# Sheet1.net
KiCad netlist of a schematic drawn in Altium Designer
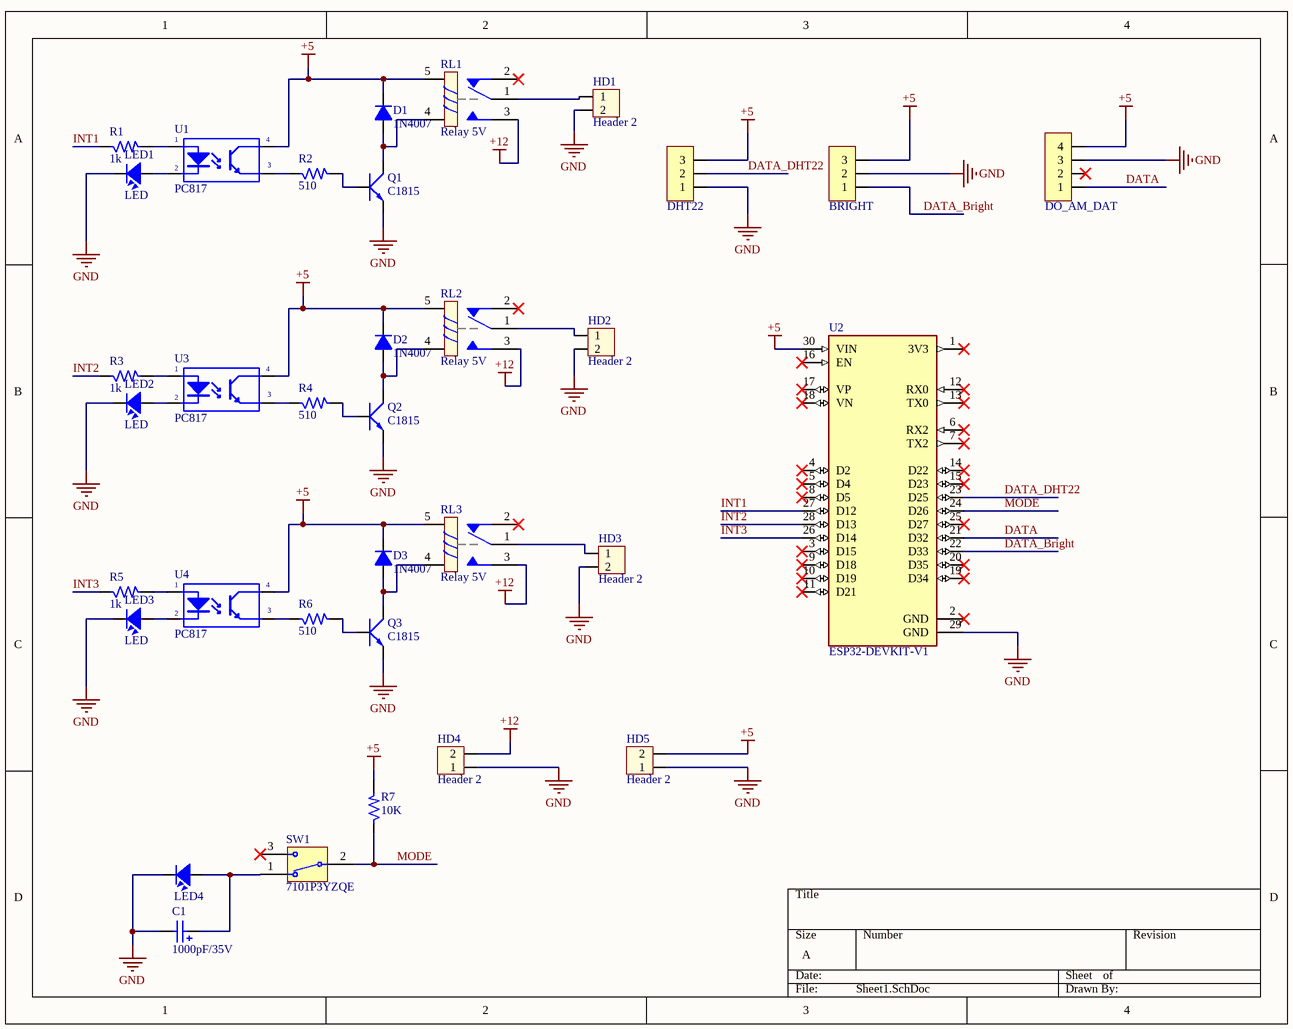
[diagram p0: Sheet1.SchDoc]

(export (version "E")
  (design (tool "Eeschema 10.0.6"))
  (components
    (comp (ref "C1")
      (value "1000pF/35V")
      (footprint "CP2/5")
      (description "Polarized Capacitor (Surface Mount)")
      (fields (field (name "Comment") "Cap Pol3") (field (name "PUBLISHER") "Altium Limited"))
      (libsource (lib "myLib_v1") (part "Cap Pol3"))
    )
    (comp (ref "D1")
      (value "1N4007")
      (footprint "D2A")
      (description "Diode 1A")
      (libsource (lib "syhaunguyen") (part "D1A"))
    )
    (comp (ref "D2")
      (value "1N4007")
      (footprint "D2A")
      (description "Diode 1A")
      (libsource (lib "syhaunguyen") (part "D1A"))
    )
    (comp (ref "D3")
      (value "1N4007")
      (footprint "D2A")
      (description "Diode 1A")
      (libsource (lib "syhaunguyen") (part "D1A"))
    )
    (comp (ref "HD1")
      (value "Header 2")
      (footprint "HED2")
      (description "Header 2 (Green)")
      (libsource (lib "") (part "Hed2_1"))
    )
    (comp (ref "HD2")
      (value "Header 2")
      (footprint "HED2")
      (description "Header 2 (Green)")
      (libsource (lib "") (part "Hed2_1"))
    )
    (comp (ref "HD3")
      (value "Header 2")
      (footprint "HED2")
      (description "Header 2 (Green)")
      (libsource (lib "") (part "Hed2_1"))
    )
    (comp (ref "HD4")
      (value "Header 2")
      (footprint "HED2")
      (description "Header 2 (Green)")
      (libsource (lib "syhaunguyen") (part "Hed2"))
    )
    (comp (ref "HD5")
      (value "Header 2")
      (footprint "HED2")
      (description "Header 2 (Green)")
      (libsource (lib "syhaunguyen") (part "Hed2"))
    )
    (comp (ref "JP1")
      (value "DO_AM_DAT")
      (footprint "JP 1x4 CT")
      (description "Cắm")
      (libsource (lib "Altium_Lib_by_KhueNguyenCreator") (part "JP 1x4 2.54 Cai Thang"))
    )
    (comp (ref "JP2")
      (value "DHT22")
      (footprint "JP 1x3 CT")
      (description "Cắm")
      (libsource (lib "Altium_Lib_by_KhueNguyenCreator") (part "JP 1x3 2.54 Cai Thang"))
    )
    (comp (ref "JP3")
      (value "BRIGHT")
      (footprint "JP 1x3 CT")
      (description "Cắm")
      (libsource (lib "Altium_Lib_by_KhueNguyenCreator") (part "JP 1x3 2.54 Cai Thang"))
    )
    (comp (ref "LED1")
      (value "LED")
      (footprint "LED-5TRED")
      (description "LED Single colour Green and Red")
      (libsource (lib "syhaunguyen") (part "LED"))
    )
    (comp (ref "LED2")
      (value "LED")
      (footprint "LED-5TRED")
      (description "LED Single colour Green and Red")
      (libsource (lib "syhaunguyen") (part "LED"))
    )
    (comp (ref "LED3")
      (value "LED")
      (footprint "LED-5TRED")
      (description "LED Single colour Green and Red")
      (libsource (lib "syhaunguyen") (part "LED"))
    )
    (comp (ref "LED4")
      (value "LED")
      (footprint "LED-5-RED")
      (description "LED Single colour Green and Red")
      (libsource (lib "Thuvien3D") (part "LED"))
    )
    (comp (ref "Q1")
      (value "C1815")
      (footprint "QTO-92")
      (description "NPN 600mW, ECB")
      (libsource (lib "syhaunguyen") (part "C1815"))
    )
    (comp (ref "Q2")
      (value "C1815")
      (footprint "QTO-92")
      (description "NPN 600mW, ECB")
      (libsource (lib "syhaunguyen") (part "C1815"))
    )
    (comp (ref "Q3")
      (value "C1815")
      (footprint "QTO-92")
      (description "NPN 600mW, ECB")
      (libsource (lib "syhaunguyen") (part "C1815"))
    )
    (comp (ref "R1")
      (value "1k")
      (footprint "DIEN TRO 1/4 W")
      (description "Resistor 1/4W")
      (libsource (lib "Cty1") (part "Res"))
    )
    (comp (ref "R2")
      (value "510")
      (footprint "DIEN TRO 1/4 W")
      (description "Resistor 1/4W")
      (libsource (lib "Cty1") (part "Res"))
    )
    (comp (ref "R3")
      (value "1k")
      (footprint "DIEN TRO 1/4 W")
      (description "Resistor 1/4W")
      (libsource (lib "Cty1") (part "Res"))
    )
    (comp (ref "R4")
      (value "510")
      (footprint "DIEN TRO 1/4 W")
      (description "Resistor 1/4W")
      (libsource (lib "Cty1") (part "Res"))
    )
    (comp (ref "R5")
      (value "1k")
      (footprint "DIEN TRO 1/4 W")
      (description "Resistor 1/4W")
      (libsource (lib "Cty1") (part "Res"))
    )
    (comp (ref "R6")
      (value "510")
      (footprint "DIEN TRO 1/4 W")
      (description "Resistor 1/4W")
      (libsource (lib "Cty1") (part "Res"))
    )
    (comp (ref "R7")
      (value "10K")
      (footprint "DIEN TRO 1/4 W")
      (description "Resistor 1/4W")
      (libsource (lib "Cty1") (part "Res"))
    )
    (comp (ref "RL1")
      (value "Relay 5V")
      (footprint "RL_SPDT_10A")
      (description "Relay SPDT,10A - 12VDC 5 Pin")
      (libsource (lib "syhaunguyen") (part "Relay 1"))
    )
    (comp (ref "RL2")
      (value "Relay 5V")
      (footprint "RL_SPDT_10A")
      (description "Relay SPDT,10A - 12VDC 5 Pin")
      (libsource (lib "syhaunguyen") (part "Relay 1"))
    )
    (comp (ref "RL3")
      (value "Relay 5V")
      (footprint "RL_SPDT_10A")
      (description "Relay SPDT,10A - 12VDC 5 Pin")
      (libsource (lib "syhaunguyen") (part "Relay 1"))
    )
    (comp (ref "SW1")
      (value "7101P3YZQE")
      (footprint "SW_TOGGLE_7101P3YZQE")
      (description "SWITCH TOGGLE SPDT 5A 120V")
      (fields (field (name "MANUFACTURER") "C&K"))
      (libsource (lib "KhanhBK_SCH_Lib_6") (part "SW_TOGGLE_7101P3YZQE"))
    )
    (comp (ref "U1")
      (value "PC817")
      (footprint "DIP4/W0.3")
      (description "Single Opto")
      (libsource (lib "syhaunguyen") (part "PC817"))
    )
    (comp (ref "U2")
      (value "ESP32-DEVKIT-V1")
      (footprint "MODULE_ESP32_DEVKIT_V1")
      (fields (field (name "MF") "Do it"))
      (libsource (lib "ESP32-DEVKIT-V1") (part "ESP32-DEVKIT-V1"))
    )
    (comp (ref "U3")
      (value "PC817")
      (footprint "DIP4/W0.3")
      (description "Single Opto")
      (libsource (lib "syhaunguyen") (part "PC817"))
    )
    (comp (ref "U4")
      (value "PC817")
      (footprint "DIP4/W0.3")
      (description "Single Opto")
      (libsource (lib "syhaunguyen") (part "PC817"))
    )
  )
  (nets
    (net (code "1") (name "+5") (class "Default")
      (node (ref "D1") (pin "2") (pinfunction "K_2") (pintype "passive"))
      (node (ref "D2") (pin "2") (pinfunction "K_2") (pintype "passive"))
      (node (ref "D3") (pin "2") (pinfunction "K_2") (pintype "passive"))
      (node (ref "HD5") (pin "2") (pinfunction "2_2") (pintype "passive"))
      (node (ref "JP1") (pin "4") (pinfunction "4_4") (pintype "passive"))
      (node (ref "JP2") (pin "3") (pinfunction "3_3") (pintype "passive"))
      (node (ref "JP3") (pin "3") (pinfunction "3_3") (pintype "passive"))
      (node (ref "R7") (pin "2") (pinfunction "2_2") (pintype "passive"))
      (node (ref "RL1") (pin "5") (pinfunction "5_5") (pintype "passive"))
      (node (ref "RL2") (pin "5") (pinfunction "5_5") (pintype "passive"))
      (node (ref "RL3") (pin "5") (pinfunction "5_5") (pintype "passive"))
      (node (ref "U1") (pin "4") (pinfunction "C_4") (pintype "passive"))
      (node (ref "U2") (pin "30") (pinfunction "VIN_30") (pintype "input"))
      (node (ref "U3") (pin "4") (pinfunction "C_4") (pintype "passive"))
      (node (ref "U4") (pin "4") (pinfunction "C_4") (pintype "passive"))
    )
    (net (code "2") (name "+12") (class "Default")
      (node (ref "HD4") (pin "2") (pinfunction "2_2") (pintype "passive"))
      (node (ref "RL1") (pin "3") (pinfunction "3_3") (pintype "passive"))
      (node (ref "RL2") (pin "3") (pinfunction "3_3") (pintype "passive"))
      (node (ref "RL3") (pin "3") (pinfunction "3_3") (pintype "passive"))
    )
    (net (code "3") (name "/DATA") (class "Default")
      (node (ref "JP1") (pin "1") (pinfunction "1_1") (pintype "passive"))
      (node (ref "U2") (pin "21") (pinfunction "D32_21") (pintype "bidirectional"))
    )
    (net (code "4") (name "/DATA_Bright") (class "Default")
      (node (ref "JP3") (pin "1") (pinfunction "1_1") (pintype "passive"))
      (node (ref "U2") (pin "22") (pinfunction "D33_22") (pintype "bidirectional"))
    )
    (net (code "5") (name "/DATA_DHT22") (class "Default")
      (node (ref "JP2") (pin "2") (pinfunction "2_2") (pintype "passive"))
      (node (ref "U2") (pin "23") (pinfunction "D25_23") (pintype "bidirectional"))
    )
    (net (code "6") (name "/INT1") (class "Default")
      (node (ref "R1") (pin "1") (pinfunction "1_1") (pintype "passive"))
      (node (ref "U2") (pin "27") (pinfunction "D12_27") (pintype "bidirectional"))
    )
    (net (code "7") (name "/INT2") (class "Default")
      (node (ref "R3") (pin "1") (pinfunction "1_1") (pintype "passive"))
      (node (ref "U2") (pin "28") (pinfunction "D13_28") (pintype "bidirectional"))
    )
    (net (code "8") (name "/INT3") (class "Default")
      (node (ref "R5") (pin "1") (pinfunction "1_1") (pintype "passive"))
      (node (ref "U2") (pin "26") (pinfunction "D14_26") (pintype "bidirectional"))
    )
    (net (code "9") (name "/MODE") (class "Default")
      (node (ref "R7") (pin "1") (pinfunction "1_1") (pintype "passive"))
      (node (ref "SW1") (pin "2") (pinfunction "COM_2") (pintype "passive"))
      (node (ref "U2") (pin "24") (pinfunction "D26_24") (pintype "bidirectional"))
    )
    (net (code "10") (name "GND") (class "Default")
      (node (ref "C1") (pin "2") (pinfunction "2_2") (pintype "passive"))
      (node (ref "HD1") (pin "2") (pinfunction "2_2") (pintype "passive"))
      (node (ref "HD2") (pin "2") (pinfunction "2_2") (pintype "passive"))
      (node (ref "HD3") (pin "2") (pinfunction "2_2") (pintype "passive"))
      (node (ref "HD4") (pin "1") (pinfunction "1_1") (pintype "passive"))
      (node (ref "HD5") (pin "1") (pinfunction "1_1") (pintype "passive"))
      (node (ref "JP1") (pin "3") (pinfunction "3_3") (pintype "passive"))
      (node (ref "JP2") (pin "1") (pinfunction "1_1") (pintype "passive"))
      (node (ref "JP3") (pin "2") (pinfunction "2_2") (pintype "passive"))
      (node (ref "LED1") (pin "2") (pinfunction "2_2") (pintype "passive"))
      (node (ref "LED2") (pin "2") (pinfunction "2_2") (pintype "passive"))
      (node (ref "LED3") (pin "2") (pinfunction "2_2") (pintype "passive"))
      (node (ref "LED4") (pin "2") (pinfunction "2_2") (pintype "passive"))
      (node (ref "Q1") (pin "1") (pinfunction "E_1") (pintype "passive"))
      (node (ref "Q2") (pin "1") (pinfunction "E_1") (pintype "passive"))
      (node (ref "Q3") (pin "1") (pinfunction "E_1") (pintype "passive"))
      (node (ref "U2") (pin "29") (pinfunction "GND_29") (pintype "power_in"))
    )
    (net (code "11") (name "Net-(D1-A)") (class "Default")
      (node (ref "D1") (pin "1") (pinfunction "A_1") (pintype "passive"))
      (node (ref "Q1") (pin "2") (pinfunction "C_2") (pintype "passive"))
      (node (ref "RL1") (pin "4") (pinfunction "4_4") (pintype "passive"))
    )
    (net (code "12") (name "Net-(D2-A)") (class "Default")
      (node (ref "D2") (pin "1") (pinfunction "A_1") (pintype "passive"))
      (node (ref "Q2") (pin "2") (pinfunction "C_2") (pintype "passive"))
      (node (ref "RL2") (pin "4") (pinfunction "4_4") (pintype "passive"))
    )
    (net (code "13") (name "Net-(D3-A)") (class "Default")
      (node (ref "D3") (pin "1") (pinfunction "A_1") (pintype "passive"))
      (node (ref "Q3") (pin "2") (pinfunction "C_2") (pintype "passive"))
      (node (ref "RL3") (pin "4") (pinfunction "4_4") (pintype "passive"))
    )
    (net (code "14") (name "Net-(HD1-Pad1)") (class "Default")
      (node (ref "HD1") (pin "1") (pinfunction "1_1") (pintype "passive"))
      (node (ref "RL1") (pin "1") (pinfunction "1_1") (pintype "passive"))
    )
    (net (code "15") (name "Net-(HD2-Pad1)") (class "Default")
      (node (ref "HD2") (pin "1") (pinfunction "1_1") (pintype "passive"))
      (node (ref "RL2") (pin "1") (pinfunction "1_1") (pintype "passive"))
    )
    (net (code "16") (name "Net-(HD3-Pad1)") (class "Default")
      (node (ref "HD3") (pin "1") (pinfunction "1_1") (pintype "passive"))
      (node (ref "RL3") (pin "1") (pinfunction "1_1") (pintype "passive"))
    )
    (net (code "17") (name "Net-(Q1-B)") (class "Default")
      (node (ref "Q1") (pin "3") (pinfunction "B_3") (pintype "passive"))
      (node (ref "R2") (pin "2") (pinfunction "2_2") (pintype "passive"))
    )
    (net (code "18") (name "Net-(Q2-B)") (class "Default")
      (node (ref "Q2") (pin "3") (pinfunction "B_3") (pintype "passive"))
      (node (ref "R4") (pin "2") (pinfunction "2_2") (pintype "passive"))
    )
    (net (code "19") (name "Net-(Q3-B)") (class "Default")
      (node (ref "Q3") (pin "3") (pinfunction "B_3") (pintype "passive"))
      (node (ref "R6") (pin "2") (pinfunction "2_2") (pintype "passive"))
    )
    (net (code "20") (name "Net-(SW1-NC)") (class "Default")
      (node (ref "C1") (pin "1") (pinfunction "1_1") (pintype "passive"))
      (node (ref "LED4") (pin "1") (pinfunction "1_1") (pintype "passive"))
      (node (ref "SW1") (pin "1") (pinfunction "NC_1") (pintype "passive"))
    )
    (net (code "21") (name "Net-(U1-A)") (class "Default")
      (node (ref "R1") (pin "2") (pinfunction "2_2") (pintype "passive"))
      (node (ref "U1") (pin "1") (pinfunction "A_1") (pintype "passive"))
    )
    (net (code "22") (name "Net-(U1-E)") (class "Default")
      (node (ref "R2") (pin "1") (pinfunction "1_1") (pintype "passive"))
      (node (ref "U1") (pin "3") (pinfunction "E_3") (pintype "passive"))
    )
    (net (code "23") (name "Net-(U1-K)") (class "Default")
      (node (ref "LED1") (pin "1") (pinfunction "1_1") (pintype "passive"))
      (node (ref "U1") (pin "2") (pinfunction "K_2") (pintype "passive"))
    )
    (net (code "24") (name "Net-(U3-A)") (class "Default")
      (node (ref "R3") (pin "2") (pinfunction "2_2") (pintype "passive"))
      (node (ref "U3") (pin "1") (pinfunction "A_1") (pintype "passive"))
    )
    (net (code "25") (name "Net-(U3-E)") (class "Default")
      (node (ref "R4") (pin "1") (pinfunction "1_1") (pintype "passive"))
      (node (ref "U3") (pin "3") (pinfunction "E_3") (pintype "passive"))
    )
    (net (code "26") (name "Net-(U3-K)") (class "Default")
      (node (ref "LED2") (pin "1") (pinfunction "1_1") (pintype "passive"))
      (node (ref "U3") (pin "2") (pinfunction "K_2") (pintype "passive"))
    )
    (net (code "27") (name "Net-(U4-A)") (class "Default")
      (node (ref "R5") (pin "2") (pinfunction "2_2") (pintype "passive"))
      (node (ref "U4") (pin "1") (pinfunction "A_1") (pintype "passive"))
    )
    (net (code "28") (name "Net-(U4-E)") (class "Default")
      (node (ref "R6") (pin "1") (pinfunction "1_1") (pintype "passive"))
      (node (ref "U4") (pin "3") (pinfunction "E_3") (pintype "passive"))
    )
    (net (code "29") (name "Net-(U4-K)") (class "Default")
      (node (ref "LED3") (pin "1") (pinfunction "1_1") (pintype "passive"))
      (node (ref "U4") (pin "2") (pinfunction "K_2") (pintype "passive"))
    )
    (net (code "30") (name "unconnected-(JP1-Pad2)") (class "Default")
      (node (ref "JP1") (pin "2") (pinfunction "2_2") (pintype "passive+no_connect"))
    )
    (net (code "31") (name "unconnected-(RL1-Pad2)") (class "Default")
      (node (ref "RL1") (pin "2") (pinfunction "2_2") (pintype "passive+no_connect"))
    )
    (net (code "32") (name "unconnected-(RL2-Pad2)") (class "Default")
      (node (ref "RL2") (pin "2") (pinfunction "2_2") (pintype "passive+no_connect"))
    )
    (net (code "33") (name "unconnected-(RL3-Pad2)") (class "Default")
      (node (ref "RL3") (pin "2") (pinfunction "2_2") (pintype "passive+no_connect"))
    )
    (net (code "34") (name "unconnected-(SW1-NO-Pad3)") (class "Default")
      (node (ref "SW1") (pin "3") (pinfunction "NO_3") (pintype "passive+no_connect"))
    )
    (net (code "35") (name "unconnected-(U2-3V3-Pad1)") (class "Default")
      (node (ref "U2") (pin "1") (pinfunction "3V3_1") (pintype "output+no_connect"))
    )
    (net (code "36") (name "unconnected-(U2-D2-Pad4)") (class "Default")
      (node (ref "U2") (pin "4") (pinfunction "D2_4") (pintype "bidirectional+no_connect"))
    )
    (net (code "37") (name "unconnected-(U2-D4-Pad5)") (class "Default")
      (node (ref "U2") (pin "5") (pinfunction "D4_5") (pintype "bidirectional+no_connect"))
    )
    (net (code "38") (name "unconnected-(U2-D5-Pad8)") (class "Default")
      (node (ref "U2") (pin "8") (pinfunction "D5_8") (pintype "bidirectional+no_connect"))
    )
    (net (code "39") (name "unconnected-(U2-D15-Pad3)") (class "Default")
      (node (ref "U2") (pin "3") (pinfunction "D15_3") (pintype "bidirectional+no_connect"))
    )
    (net (code "40") (name "unconnected-(U2-D18-Pad9)") (class "Default")
      (node (ref "U2") (pin "9") (pinfunction "D18_9") (pintype "bidirectional+no_connect"))
    )
    (net (code "41") (name "unconnected-(U2-D19-Pad10)") (class "Default")
      (node (ref "U2") (pin "10") (pinfunction "D19_10") (pintype "bidirectional+no_connect"))
    )
    (net (code "42") (name "unconnected-(U2-D21-Pad11)") (class "Default")
      (node (ref "U2") (pin "11") (pinfunction "D21_11") (pintype "bidirectional+no_connect"))
    )
    (net (code "43") (name "unconnected-(U2-D22-Pad14)") (class "Default")
      (node (ref "U2") (pin "14") (pinfunction "D22_14") (pintype "bidirectional+no_connect"))
    )
    (net (code "44") (name "unconnected-(U2-D23-Pad15)") (class "Default")
      (node (ref "U2") (pin "15") (pinfunction "D23_15") (pintype "bidirectional+no_connect"))
    )
    (net (code "45") (name "unconnected-(U2-D27-Pad25)") (class "Default")
      (node (ref "U2") (pin "25") (pinfunction "D27_25") (pintype "bidirectional+no_connect"))
    )
    (net (code "46") (name "unconnected-(U2-D34-Pad19)") (class "Default")
      (node (ref "U2") (pin "19") (pinfunction "D34_19") (pintype "bidirectional+no_connect"))
    )
    (net (code "47") (name "unconnected-(U2-D35-Pad20)") (class "Default")
      (node (ref "U2") (pin "20") (pinfunction "D35_20") (pintype "bidirectional+no_connect"))
    )
    (net (code "48") (name "unconnected-(U2-EN-Pad16)") (class "Default")
      (node (ref "U2") (pin "16") (pinfunction "EN_16") (pintype "input+no_connect"))
    )
    (net (code "49") (name "unconnected-(U2-GND-Pad2)") (class "Default")
      (node (ref "U2") (pin "2") (pinfunction "GND_2") (pintype "power_in+no_connect"))
    )
    (net (code "50") (name "unconnected-(U2-RX0-Pad12)") (class "Default")
      (node (ref "U2") (pin "12") (pinfunction "RX0_12") (pintype "input+no_connect"))
    )
    (net (code "51") (name "unconnected-(U2-RX2-Pad6)") (class "Default")
      (node (ref "U2") (pin "6") (pinfunction "RX2_6") (pintype "input+no_connect"))
    )
    (net (code "52") (name "unconnected-(U2-TX0-Pad13)") (class "Default")
      (node (ref "U2") (pin "13") (pinfunction "TX0_13") (pintype "output+no_connect"))
    )
    (net (code "53") (name "unconnected-(U2-TX2-Pad7)") (class "Default")
      (node (ref "U2") (pin "7") (pinfunction "TX2_7") (pintype "output+no_connect"))
    )
    (net (code "54") (name "unconnected-(U2-VN-Pad18)") (class "Default")
      (node (ref "U2") (pin "18") (pinfunction "VN_18") (pintype "bidirectional+no_connect"))
    )
    (net (code "55") (name "unconnected-(U2-VP-Pad17)") (class "Default")
      (node (ref "U2") (pin "17") (pinfunction "VP_17") (pintype "bidirectional+no_connect"))
    )
  )
)
